# Schematic.net
KiCad netlist of a schematic drawn in Altium Designer
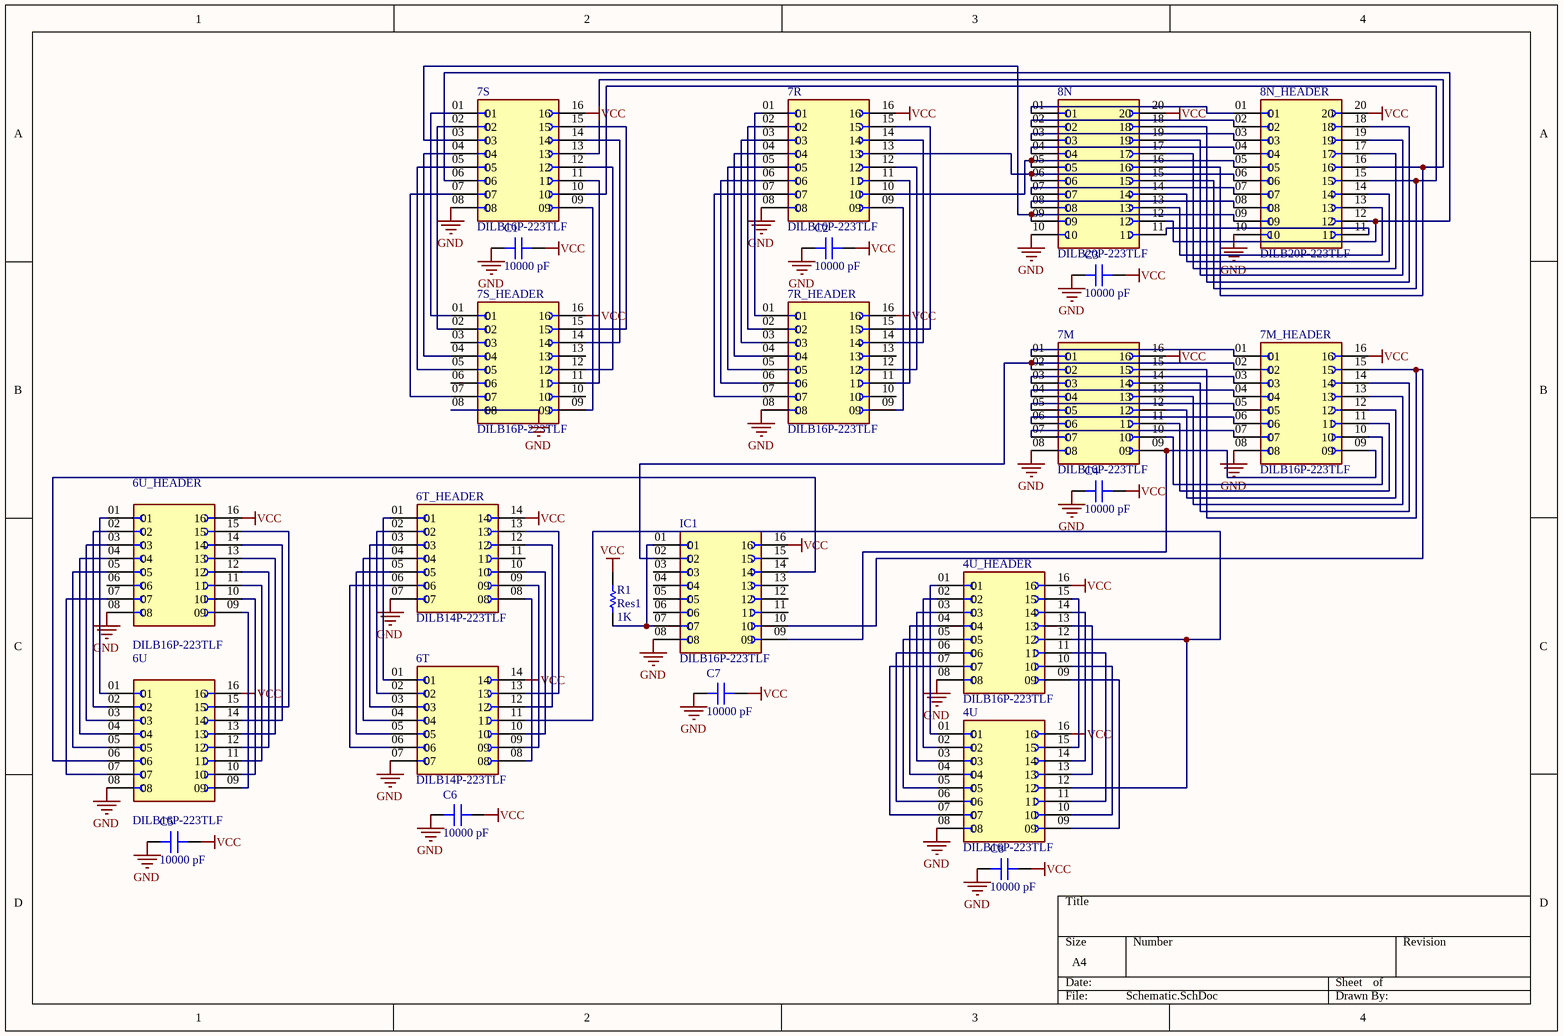
[diagram p0: Schematic.SchDoc]

(export (version "E")
  (design (tool "Eeschema 10.0.6"))
  (components
    (comp (ref "4U")
      (value "DILB16P-223TLF")
      (footprint "AMPHENOL_DILB16P-223TLF")
      (description "DIP Socket, Stamped and Formed")
      (fields (field (name "MF") "Amphenol ICC (FCI)"))
      (libsource (lib "DILB16P-223TLF") (part "DILB16P-223TLF"))
    )
    (comp (ref "4U_HEADER")
      (value "DILB16P-223TLF")
      (footprint "AMPHENOL_DILB16P-223TLF")
      (description "DIP Socket, Stamped and Formed")
      (fields (field (name "MF") "Amphenol ICC (FCI)"))
      (libsource (lib "DILB16P-223TLF") (part "DILB16P-223TLF"))
    )
    (comp (ref "6T")
      (value "DILB14P-223TLF")
      (footprint "AMPHENOL_DILB14P-223TLF")
      (libsource (lib "DILB14P-223TLF") (part "DILB14P-223TLF"))
    )
    (comp (ref "6T_HEADER")
      (value "DILB14P-223TLF")
      (footprint "AMPHENOL_DILB14P-223TLF")
      (libsource (lib "DILB14P-223TLF") (part "DILB14P-223TLF"))
    )
    (comp (ref "6U")
      (value "DILB16P-223TLF")
      (footprint "AMPHENOL_DILB16P-223TLF")
      (description "DIP Socket, Stamped and Formed")
      (fields (field (name "MF") "Amphenol ICC (FCI)"))
      (libsource (lib "DILB16P-223TLF") (part "DILB16P-223TLF"))
    )
    (comp (ref "6U_HEADER")
      (value "DILB16P-223TLF")
      (footprint "AMPHENOL_DILB16P-223TLF")
      (description "DIP Socket, Stamped and Formed")
      (fields (field (name "MF") "Amphenol ICC (FCI)"))
      (libsource (lib "DILB16P-223TLF") (part "DILB16P-223TLF"))
    )
    (comp (ref "7M")
      (value "DILB16P-223TLF")
      (footprint "AMPHENOL_DILB16P-223TLF")
      (description "DIP Socket, Stamped and Formed")
      (fields (field (name "MF") "Amphenol ICC (FCI)"))
      (libsource (lib "DILB16P-223TLF") (part "DILB16P-223TLF"))
    )
    (comp (ref "7M_HEADER")
      (value "DILB16P-223TLF")
      (footprint "AMPHENOL_DILB16P-223TLF")
      (description "DIP Socket, Stamped and Formed")
      (fields (field (name "MF") "Amphenol ICC (FCI)"))
      (libsource (lib "DILB16P-223TLF") (part "DILB16P-223TLF"))
    )
    (comp (ref "7R")
      (value "DILB16P-223TLF")
      (footprint "AMPHENOL_DILB16P-223TLF")
      (description "DIP Socket, Stamped and Formed")
      (fields (field (name "MF") "Amphenol ICC (FCI)"))
      (libsource (lib "DILB16P-223TLF") (part "DILB16P-223TLF"))
    )
    (comp (ref "7R_HEADER")
      (value "DILB16P-223TLF")
      (footprint "AMPHENOL_DILB16P-223TLF")
      (description "DIP Socket, Stamped and Formed")
      (fields (field (name "MF") "Amphenol ICC (FCI)"))
      (libsource (lib "DILB16P-223TLF") (part "DILB16P-223TLF"))
    )
    (comp (ref "7S")
      (value "DILB16P-223TLF")
      (footprint "AMPHENOL_DILB16P-223TLF")
      (description "DIP Socket, Stamped and Formed")
      (fields (field (name "MF") "Amphenol ICC (FCI)"))
      (libsource (lib "DILB16P-223TLF") (part "DILB16P-223TLF"))
    )
    (comp (ref "7S_HEADER")
      (value "DILB16P-223TLF")
      (footprint "AMPHENOL_DILB16P-223TLF")
      (description "DIP Socket, Stamped and Formed")
      (fields (field (name "MF") "Amphenol ICC (FCI)"))
      (libsource (lib "DILB16P-223TLF") (part "DILB16P-223TLF"))
    )
    (comp (ref "8N")
      (value "DILB20P-223TLF")
      (footprint "AMPHENOL_DILB20P-223TLF")
      (description "20 (2 x 10) Pos DIP, 0.3 (7.62mm) Row Spacing Socket Tin Through Hole")
      (fields (field (name "MF") "FCI"))
      (libsource (lib "DILB20P-223TLF") (part "DILB20P-223TLF"))
    )
    (comp (ref "8N_HEADER")
      (value "DILB20P-223TLF")
      (footprint "AMPHENOL_DILB20P-223TLF")
      (description "20 (2 x 10) Pos DIP, 0.3 (7.62mm) Row Spacing Socket Tin Through Hole")
      (fields (field (name "MF") "FCI"))
      (libsource (lib "DILB20P-223TLF") (part "DILB20P-223TLF"))
    )
    (comp (ref "C1")
      (value "10000 pF")
      (footprint "CAP FILM 0805")
      (description "CAP FILM 10000PF 2% 16VDC 0805")
      (fields
        (field (name "PART NUMBER") "ECH-U1C103GX5")
        (field (name "CAPACITANCE") "10000 pF")
        (field (name "MANUFACTURER") "Panasonic Electronic Components")
      )
      (libsource (lib "Celestial Altium Library - altium_library") (part "Capacitor"))
    )
    (comp (ref "C2")
      (value "10000 pF")
      (footprint "CAP FILM 0805")
      (description "CAP FILM 10000PF 2% 16VDC 0805")
      (fields
        (field (name "PART NUMBER") "ECH-U1C103GX5")
        (field (name "CAPACITANCE") "10000 pF")
        (field (name "MANUFACTURER") "Panasonic Electronic Components")
      )
      (libsource (lib "Celestial Altium Library - altium_library") (part "Capacitor"))
    )
    (comp (ref "C3")
      (value "10000 pF")
      (footprint "CAP FILM 0805")
      (description "CAP FILM 10000PF 2% 16VDC 0805")
      (fields
        (field (name "PART NUMBER") "ECH-U1C103GX5")
        (field (name "CAPACITANCE") "10000 pF")
        (field (name "MANUFACTURER") "Panasonic Electronic Components")
      )
      (libsource (lib "Celestial Altium Library - altium_library") (part "Capacitor"))
    )
    (comp (ref "C4")
      (value "10000 pF")
      (footprint "CAP FILM 0805")
      (description "CAP FILM 10000PF 2% 16VDC 0805")
      (fields
        (field (name "PART NUMBER") "ECH-U1C103GX5")
        (field (name "CAPACITANCE") "10000 pF")
        (field (name "MANUFACTURER") "Panasonic Electronic Components")
      )
      (libsource (lib "Celestial Altium Library - altium_library") (part "Capacitor"))
    )
    (comp (ref "C5")
      (value "10000 pF")
      (footprint "CAP FILM 0805")
      (description "CAP FILM 10000PF 2% 16VDC 0805")
      (fields
        (field (name "PART NUMBER") "ECH-U1C103GX5")
        (field (name "CAPACITANCE") "10000 pF")
        (field (name "MANUFACTURER") "Panasonic Electronic Components")
      )
      (libsource (lib "Celestial Altium Library - altium_library") (part "Capacitor"))
    )
    (comp (ref "C6")
      (value "10000 pF")
      (footprint "CAP FILM 0805")
      (description "CAP FILM 10000PF 2% 16VDC 0805")
      (fields
        (field (name "PART NUMBER") "ECH-U1C103GX5")
        (field (name "CAPACITANCE") "10000 pF")
        (field (name "MANUFACTURER") "Panasonic Electronic Components")
      )
      (libsource (lib "Celestial Altium Library - altium_library") (part "Capacitor"))
    )
    (comp (ref "C7")
      (value "10000 pF")
      (footprint "CAP FILM 0805")
      (description "CAP FILM 10000PF 2% 16VDC 0805")
      (fields
        (field (name "PART NUMBER") "ECH-U1C103GX5")
        (field (name "CAPACITANCE") "10000 pF")
        (field (name "MANUFACTURER") "Panasonic Electronic Components")
      )
      (libsource (lib "Celestial Altium Library - altium_library") (part "Capacitor"))
    )
    (comp (ref "C8")
      (value "10000 pF")
      (footprint "CAP FILM 0805")
      (description "CAP FILM 10000PF 2% 16VDC 0805")
      (fields
        (field (name "PART NUMBER") "ECH-U1C103GX5")
        (field (name "CAPACITANCE") "10000 pF")
        (field (name "MANUFACTURER") "Panasonic Electronic Components")
      )
      (libsource (lib "Celestial Altium Library - altium_library") (part "Capacitor"))
    )
    (comp (ref "IC1")
      (value "DILB16P-223TLF")
      (footprint "AMPHENOL_DILB16P-223TLF")
      (description "DIP Socket, Stamped and Formed")
      (fields (field (name "MF") "Amphenol ICC (FCI)"))
      (libsource (lib "DILB16P-223TLF") (part "DILB16P-223TLF"))
    )
    (comp (ref "R1")
      (value "Res1")
      (footprint "AXIAL-0.3")
      (description "Resistor")
      (fields (field (name "ALTIUM_VALUE") "1K") (field (name "PUBLISHER") "Altium Limited"))
      (libsource (lib "Miscellaneous Devices") (part "Res1"))
    )
  )
  (nets
    (net (code "1") (name "GND") (class "Default")
      (node (ref "4U") (pin "08") (pinfunction "08_08") (pintype "passive"))
      (node (ref "4U_HEADER") (pin "08") (pinfunction "08_08") (pintype "passive"))
      (node (ref "6T") (pin "07") (pinfunction "07_07") (pintype "passive"))
      (node (ref "6T_HEADER") (pin "07") (pinfunction "07_07") (pintype "passive"))
      (node (ref "6U") (pin "08") (pinfunction "08_08") (pintype "passive"))
      (node (ref "6U_HEADER") (pin "08") (pinfunction "08_08") (pintype "passive"))
      (node (ref "7M") (pin "08") (pinfunction "08_08") (pintype "passive"))
      (node (ref "7M_HEADER") (pin "08") (pinfunction "08_08") (pintype "passive"))
      (node (ref "7R") (pin "08") (pinfunction "08_08") (pintype "passive"))
      (node (ref "7R_HEADER") (pin "08") (pinfunction "08_08") (pintype "passive"))
      (node (ref "7S") (pin "08") (pinfunction "08_08") (pintype "passive"))
      (node (ref "7S_HEADER") (pin "08") (pinfunction "08_08") (pintype "passive"))
      (node (ref "8N") (pin "10") (pinfunction "10_10") (pintype "passive"))
      (node (ref "8N_HEADER") (pin "10") (pinfunction "10_10") (pintype "passive"))
      (node (ref "C1") (pin "1") (pinfunction "1_1") (pintype "passive"))
      (node (ref "C2") (pin "1") (pinfunction "1_1") (pintype "passive"))
      (node (ref "C3") (pin "1") (pinfunction "1_1") (pintype "passive"))
      (node (ref "C4") (pin "1") (pinfunction "1_1") (pintype "passive"))
      (node (ref "C5") (pin "1") (pinfunction "1_1") (pintype "passive"))
      (node (ref "C6") (pin "1") (pinfunction "1_1") (pintype "passive"))
      (node (ref "C7") (pin "1") (pinfunction "1_1") (pintype "passive"))
      (node (ref "C8") (pin "1") (pinfunction "1_1") (pintype "passive"))
      (node (ref "IC1") (pin "08") (pinfunction "08_08") (pintype "passive"))
    )
    (net (code "2") (name "Net-(4U-Pad01)") (class "Default")
      (node (ref "4U") (pin "01") (pinfunction "01_01") (pintype "passive"))
      (node (ref "4U_HEADER") (pin "01") (pinfunction "01_01") (pintype "passive"))
    )
    (net (code "3") (name "Net-(4U-Pad02)") (class "Default")
      (node (ref "4U") (pin "02") (pinfunction "02_02") (pintype "passive"))
      (node (ref "4U_HEADER") (pin "02") (pinfunction "02_02") (pintype "passive"))
    )
    (net (code "4") (name "Net-(4U-Pad03)") (class "Default")
      (node (ref "4U") (pin "03") (pinfunction "03_03") (pintype "passive"))
      (node (ref "4U_HEADER") (pin "03") (pinfunction "03_03") (pintype "passive"))
    )
    (net (code "5") (name "Net-(4U-Pad04)") (class "Default")
      (node (ref "4U") (pin "04") (pinfunction "04_04") (pintype "passive"))
      (node (ref "4U_HEADER") (pin "04") (pinfunction "04_04") (pintype "passive"))
    )
    (net (code "6") (name "Net-(4U-Pad05)") (class "Default")
      (node (ref "4U") (pin "05") (pinfunction "05_05") (pintype "passive"))
      (node (ref "4U_HEADER") (pin "05") (pinfunction "05_05") (pintype "passive"))
    )
    (net (code "7") (name "Net-(4U-Pad06)") (class "Default")
      (node (ref "4U") (pin "06") (pinfunction "06_06") (pintype "passive"))
      (node (ref "4U_HEADER") (pin "06") (pinfunction "06_06") (pintype "passive"))
    )
    (net (code "8") (name "Net-(4U-Pad07)") (class "Default")
      (node (ref "4U") (pin "07") (pinfunction "07_07") (pintype "passive"))
      (node (ref "4U_HEADER") (pin "07") (pinfunction "07_07") (pintype "passive"))
    )
    (net (code "9") (name "Net-(4U-Pad09)") (class "Default")
      (node (ref "4U") (pin "09") (pinfunction "09_09") (pintype "passive"))
      (node (ref "4U_HEADER") (pin "09") (pinfunction "09_09") (pintype "passive"))
    )
    (net (code "10") (name "Net-(4U-Pad10)") (class "Default")
      (node (ref "4U") (pin "10") (pinfunction "10_10") (pintype "passive"))
      (node (ref "4U_HEADER") (pin "10") (pinfunction "10_10") (pintype "passive"))
    )
    (net (code "11") (name "Net-(4U-Pad11)") (class "Default")
      (node (ref "4U") (pin "11") (pinfunction "11_11") (pintype "passive"))
      (node (ref "4U_HEADER") (pin "11") (pinfunction "11_11") (pintype "passive"))
    )
    (net (code "12") (name "Net-(4U-Pad12)") (class "Default")
      (node (ref "4U") (pin "12") (pinfunction "12_12") (pintype "passive"))
      (node (ref "4U_HEADER") (pin "12") (pinfunction "12_12") (pintype "passive"))
      (node (ref "6T") (pin "11") (pinfunction "11_11") (pintype "passive"))
    )
    (net (code "13") (name "Net-(4U-Pad13)") (class "Default")
      (node (ref "4U") (pin "13") (pinfunction "13_13") (pintype "passive"))
      (node (ref "4U_HEADER") (pin "13") (pinfunction "13_13") (pintype "passive"))
    )
    (net (code "14") (name "Net-(4U-Pad14)") (class "Default")
      (node (ref "4U") (pin "14") (pinfunction "14_14") (pintype "passive"))
      (node (ref "4U_HEADER") (pin "14") (pinfunction "14_14") (pintype "passive"))
    )
    (net (code "15") (name "Net-(4U-Pad15)") (class "Default")
      (node (ref "4U") (pin "15") (pinfunction "15_15") (pintype "passive"))
      (node (ref "4U_HEADER") (pin "15") (pinfunction "15_15") (pintype "passive"))
    )
    (net (code "16") (name "Net-(6T-Pad01)") (class "Default")
      (node (ref "6T") (pin "01") (pinfunction "01_01") (pintype "passive"))
      (node (ref "6T_HEADER") (pin "01") (pinfunction "01_01") (pintype "passive"))
    )
    (net (code "17") (name "Net-(6T-Pad02)") (class "Default")
      (node (ref "6T") (pin "02") (pinfunction "02_02") (pintype "passive"))
      (node (ref "6T_HEADER") (pin "02") (pinfunction "02_02") (pintype "passive"))
    )
    (net (code "18") (name "Net-(6T-Pad03)") (class "Default")
      (node (ref "6T") (pin "03") (pinfunction "03_03") (pintype "passive"))
      (node (ref "6T_HEADER") (pin "03") (pinfunction "03_03") (pintype "passive"))
    )
    (net (code "19") (name "Net-(6T-Pad04)") (class "Default")
      (node (ref "6T") (pin "04") (pinfunction "04_04") (pintype "passive"))
      (node (ref "6T_HEADER") (pin "04") (pinfunction "04_04") (pintype "passive"))
    )
    (net (code "20") (name "Net-(6T-Pad05)") (class "Default")
      (node (ref "6T") (pin "05") (pinfunction "05_05") (pintype "passive"))
      (node (ref "6T_HEADER") (pin "05") (pinfunction "05_05") (pintype "passive"))
    )
    (net (code "21") (name "Net-(6T-Pad06)") (class "Default")
      (node (ref "6T") (pin "06") (pinfunction "06_06") (pintype "passive"))
      (node (ref "6T_HEADER") (pin "06") (pinfunction "06_06") (pintype "passive"))
    )
    (net (code "22") (name "Net-(6T-Pad08)") (class "Default")
      (node (ref "6T") (pin "08") (pinfunction "08_08") (pintype "passive"))
      (node (ref "6T_HEADER") (pin "08") (pinfunction "08_08") (pintype "passive"))
    )
    (net (code "23") (name "Net-(6T-Pad09)") (class "Default")
      (node (ref "6T") (pin "09") (pinfunction "09_09") (pintype "passive"))
      (node (ref "6T_HEADER") (pin "09") (pinfunction "09_09") (pintype "passive"))
    )
    (net (code "24") (name "Net-(6T-Pad10)") (class "Default")
      (node (ref "6T") (pin "10") (pinfunction "10_10") (pintype "passive"))
      (node (ref "6T_HEADER") (pin "10") (pinfunction "10_10") (pintype "passive"))
    )
    (net (code "25") (name "Net-(6T-Pad12)") (class "Default")
      (node (ref "6T") (pin "12") (pinfunction "12_12") (pintype "passive"))
      (node (ref "6T_HEADER") (pin "12") (pinfunction "12_12") (pintype "passive"))
    )
    (net (code "26") (name "Net-(6T-Pad13)") (class "Default")
      (node (ref "6T") (pin "13") (pinfunction "13_13") (pintype "passive"))
      (node (ref "6T_HEADER") (pin "13") (pinfunction "13_13") (pintype "passive"))
    )
    (net (code "27") (name "Net-(6U-Pad01)") (class "Default")
      (node (ref "6U") (pin "01") (pinfunction "01_01") (pintype "passive"))
      (node (ref "6U_HEADER") (pin "01") (pinfunction "01_01") (pintype "passive"))
    )
    (net (code "28") (name "Net-(6U-Pad02)") (class "Default")
      (node (ref "6U") (pin "02") (pinfunction "02_02") (pintype "passive"))
      (node (ref "6U_HEADER") (pin "02") (pinfunction "02_02") (pintype "passive"))
    )
    (net (code "29") (name "Net-(6U-Pad03)") (class "Default")
      (node (ref "6U") (pin "03") (pinfunction "03_03") (pintype "passive"))
      (node (ref "6U_HEADER") (pin "03") (pinfunction "03_03") (pintype "passive"))
    )
    (net (code "30") (name "Net-(6U-Pad04)") (class "Default")
      (node (ref "6U") (pin "04") (pinfunction "04_04") (pintype "passive"))
      (node (ref "6U_HEADER") (pin "04") (pinfunction "04_04") (pintype "passive"))
    )
    (net (code "31") (name "Net-(6U-Pad05)") (class "Default")
      (node (ref "6U") (pin "05") (pinfunction "05_05") (pintype "passive"))
      (node (ref "6U_HEADER") (pin "05") (pinfunction "05_05") (pintype "passive"))
    )
    (net (code "32") (name "Net-(6U-Pad06)") (class "Default")
      (node (ref "6U") (pin "06") (pinfunction "06_06") (pintype "passive"))
      (node (ref "IC1") (pin "14") (pinfunction "14_14") (pintype "passive"))
    )
    (net (code "33") (name "Net-(6U-Pad07)") (class "Default")
      (node (ref "6U") (pin "07") (pinfunction "07_07") (pintype "passive"))
      (node (ref "6U_HEADER") (pin "07") (pinfunction "07_07") (pintype "passive"))
    )
    (net (code "34") (name "Net-(6U-Pad09)") (class "Default")
      (node (ref "6U") (pin "09") (pinfunction "09_09") (pintype "passive"))
      (node (ref "6U_HEADER") (pin "09") (pinfunction "09_09") (pintype "passive"))
    )
    (net (code "35") (name "Net-(6U-Pad10)") (class "Default")
      (node (ref "6U") (pin "10") (pinfunction "10_10") (pintype "passive"))
      (node (ref "6U_HEADER") (pin "10") (pinfunction "10_10") (pintype "passive"))
    )
    (net (code "36") (name "Net-(6U-Pad11)") (class "Default")
      (node (ref "6U") (pin "11") (pinfunction "11_11") (pintype "passive"))
      (node (ref "6U_HEADER") (pin "11") (pinfunction "11_11") (pintype "passive"))
    )
    (net (code "37") (name "Net-(6U-Pad12)") (class "Default")
      (node (ref "6U") (pin "12") (pinfunction "12_12") (pintype "passive"))
      (node (ref "6U_HEADER") (pin "12") (pinfunction "12_12") (pintype "passive"))
    )
    (net (code "38") (name "Net-(6U-Pad13)") (class "Default")
      (node (ref "6U") (pin "13") (pinfunction "13_13") (pintype "passive"))
      (node (ref "6U_HEADER") (pin "13") (pinfunction "13_13") (pintype "passive"))
    )
    (net (code "39") (name "Net-(6U-Pad14)") (class "Default")
      (node (ref "6U") (pin "14") (pinfunction "14_14") (pintype "passive"))
      (node (ref "6U_HEADER") (pin "14") (pinfunction "14_14") (pintype "passive"))
    )
    (net (code "40") (name "Net-(6U-Pad15)") (class "Default")
      (node (ref "6U") (pin "15") (pinfunction "15_15") (pintype "passive"))
      (node (ref "6U_HEADER") (pin "15") (pinfunction "15_15") (pintype "passive"))
    )
    (net (code "41") (name "Net-(7M-Pad01)") (class "Default")
      (node (ref "7M") (pin "01") (pinfunction "01_01") (pintype "passive"))
      (node (ref "7M_HEADER") (pin "01") (pinfunction "01_01") (pintype "passive"))
    )
    (net (code "42") (name "Net-(7M-Pad02)") (class "Default")
      (node (ref "7M") (pin "02") (pinfunction "02_02") (pintype "passive"))
      (node (ref "7M_HEADER") (pin "02") (pinfunction "02_02") (pintype "passive"))
      (node (ref "IC1") (pin "02") (pinfunction "02_02") (pintype "passive"))
    )
    (net (code "43") (name "Net-(7M-Pad03)") (class "Default")
      (node (ref "7M") (pin "03") (pinfunction "03_03") (pintype "passive"))
      (node (ref "7M_HEADER") (pin "03") (pinfunction "03_03") (pintype "passive"))
    )
    (net (code "44") (name "Net-(7M-Pad04)") (class "Default")
      (node (ref "7M") (pin "04") (pinfunction "04_04") (pintype "passive"))
      (node (ref "7M_HEADER") (pin "04") (pinfunction "04_04") (pintype "passive"))
    )
    (net (code "45") (name "Net-(7M-Pad05)") (class "Default")
      (node (ref "7M") (pin "05") (pinfunction "05_05") (pintype "passive"))
      (node (ref "7M_HEADER") (pin "05") (pinfunction "05_05") (pintype "passive"))
    )
    (net (code "46") (name "Net-(7M-Pad06)") (class "Default")
      (node (ref "7M") (pin "06") (pinfunction "06_06") (pintype "passive"))
      (node (ref "7M_HEADER") (pin "06") (pinfunction "06_06") (pintype "passive"))
    )
    (net (code "47") (name "Net-(7M-Pad07)") (class "Default")
      (node (ref "7M") (pin "07") (pinfunction "07_07") (pintype "passive"))
      (node (ref "7M_HEADER") (pin "07") (pinfunction "07_07") (pintype "passive"))
    )
    (net (code "48") (name "Net-(7M-Pad09)") (class "Default")
      (node (ref "7M") (pin "09") (pinfunction "09_09") (pintype "passive"))
      (node (ref "7M_HEADER") (pin "09") (pinfunction "09_09") (pintype "passive"))
      (node (ref "IC1") (pin "09") (pinfunction "09_09") (pintype "passive"))
    )
    (net (code "49") (name "Net-(7M-Pad10)") (class "Default")
      (node (ref "7M") (pin "10") (pinfunction "10_10") (pintype "passive"))
      (node (ref "7M_HEADER") (pin "10") (pinfunction "10_10") (pintype "passive"))
    )
    (net (code "50") (name "Net-(7M-Pad11)") (class "Default")
      (node (ref "7M") (pin "11") (pinfunction "11_11") (pintype "passive"))
      (node (ref "7M_HEADER") (pin "11") (pinfunction "11_11") (pintype "passive"))
    )
    (net (code "51") (name "Net-(7M-Pad12)") (class "Default")
      (node (ref "7M") (pin "12") (pinfunction "12_12") (pintype "passive"))
      (node (ref "7M_HEADER") (pin "12") (pinfunction "12_12") (pintype "passive"))
    )
    (net (code "52") (name "Net-(7M-Pad13)") (class "Default")
      (node (ref "7M") (pin "13") (pinfunction "13_13") (pintype "passive"))
      (node (ref "7M_HEADER") (pin "13") (pinfunction "13_13") (pintype "passive"))
    )
    (net (code "53") (name "Net-(7M-Pad14)") (class "Default")
      (node (ref "7M") (pin "14") (pinfunction "14_14") (pintype "passive"))
      (node (ref "7M_HEADER") (pin "14") (pinfunction "14_14") (pintype "passive"))
    )
    (net (code "54") (name "Net-(7M-Pad15)") (class "Default")
      (node (ref "7M") (pin "15") (pinfunction "15_15") (pintype "passive"))
      (node (ref "7M_HEADER") (pin "15") (pinfunction "15_15") (pintype "passive"))
      (node (ref "IC1") (pin "10") (pinfunction "10_10") (pintype "passive"))
    )
    (net (code "55") (name "Net-(7R-Pad01)") (class "Default")
      (node (ref "7R") (pin "01") (pinfunction "01_01") (pintype "passive"))
      (node (ref "7R_HEADER") (pin "01") (pinfunction "01_01") (pintype "passive"))
    )
    (net (code "56") (name "Net-(7R-Pad02)") (class "Default")
      (node (ref "7R") (pin "02") (pinfunction "02_02") (pintype "passive"))
      (node (ref "7R_HEADER") (pin "02") (pinfunction "02_02") (pintype "passive"))
    )
    (net (code "57") (name "Net-(7R-Pad03)") (class "Default")
      (node (ref "7R") (pin "03") (pinfunction "03_03") (pintype "passive"))
      (node (ref "7R_HEADER") (pin "03") (pinfunction "03_03") (pintype "passive"))
    )
    (net (code "58") (name "Net-(7R-Pad04)") (class "Default")
      (node (ref "7R") (pin "04") (pinfunction "04_04") (pintype "passive"))
      (node (ref "7R_HEADER") (pin "04") (pinfunction "04_04") (pintype "passive"))
    )
    (net (code "59") (name "Net-(7R-Pad05)") (class "Default")
      (node (ref "7R") (pin "05") (pinfunction "05_05") (pintype "passive"))
      (node (ref "7R_HEADER") (pin "05") (pinfunction "05_05") (pintype "passive"))
    )
    (net (code "60") (name "Net-(7R-Pad06)") (class "Default")
      (node (ref "7R") (pin "06") (pinfunction "06_06") (pintype "passive"))
      (node (ref "7R_HEADER") (pin "06") (pinfunction "06_06") (pintype "passive"))
    )
    (net (code "61") (name "Net-(7R-Pad07)") (class "Default")
      (node (ref "7R") (pin "07") (pinfunction "07_07") (pintype "passive"))
      (node (ref "7R_HEADER") (pin "07") (pinfunction "07_07") (pintype "passive"))
    )
    (net (code "62") (name "Net-(7R-Pad09)") (class "Default")
      (node (ref "7R") (pin "09") (pinfunction "09_09") (pintype "passive"))
      (node (ref "7R_HEADER") (pin "09") (pinfunction "09_09") (pintype "passive"))
    )
    (net (code "63") (name "Net-(7R-Pad10)") (class "Default")
      (node (ref "7R") (pin "10") (pinfunction "10_10") (pintype "passive"))
      (node (ref "8N") (pin "05") (pinfunction "05_05") (pintype "passive"))
      (node (ref "8N_HEADER") (pin "05") (pinfunction "05_05") (pintype "passive"))
    )
    (net (code "64") (name "Net-(7R-Pad11)") (class "Default")
      (node (ref "7R") (pin "11") (pinfunction "11_11") (pintype "passive"))
      (node (ref "7R_HEADER") (pin "11") (pinfunction "11_11") (pintype "passive"))
    )
    (net (code "65") (name "Net-(7R-Pad12)") (class "Default")
      (node (ref "7R") (pin "12") (pinfunction "12_12") (pintype "passive"))
      (node (ref "7R_HEADER") (pin "12") (pinfunction "12_12") (pintype "passive"))
    )
    (net (code "66") (name "Net-(7R-Pad13)") (class "Default")
      (node (ref "7R") (pin "13") (pinfunction "13_13") (pintype "passive"))
      (node (ref "8N") (pin "06") (pinfunction "06_06") (pintype "passive"))
      (node (ref "8N_HEADER") (pin "06") (pinfunction "06_06") (pintype "passive"))
    )
    (net (code "67") (name "Net-(7R-Pad14)") (class "Default")
      (node (ref "7R") (pin "14") (pinfunction "14_14") (pintype "passive"))
      (node (ref "7R_HEADER") (pin "14") (pinfunction "14_14") (pintype "passive"))
    )
    (net (code "68") (name "Net-(7R-Pad15)") (class "Default")
      (node (ref "7R") (pin "15") (pinfunction "15_15") (pintype "passive"))
      (node (ref "7R_HEADER") (pin "15") (pinfunction "15_15") (pintype "passive"))
    )
    (net (code "69") (name "Net-(7S-Pad01)") (class "Default")
      (node (ref "7S") (pin "01") (pinfunction "01_01") (pintype "passive"))
      (node (ref "7S_HEADER") (pin "01") (pinfunction "01_01") (pintype "passive"))
    )
    (net (code "70") (name "Net-(7S-Pad02)") (class "Default")
      (node (ref "7S") (pin "02") (pinfunction "02_02") (pintype "passive"))
      (node (ref "7S_HEADER") (pin "02") (pinfunction "02_02") (pintype "passive"))
    )
    (net (code "71") (name "Net-(7S-Pad03)") (class "Default")
      (node (ref "7S") (pin "03") (pinfunction "03_03") (pintype "passive"))
      (node (ref "8N") (pin "09") (pinfunction "09_09") (pintype "passive"))
      (node (ref "8N_HEADER") (pin "09") (pinfunction "09_09") (pintype "passive"))
    )
    (net (code "72") (name "Net-(7S-Pad04)") (class "Default")
      (node (ref "7S") (pin "04") (pinfunction "04_04") (pintype "passive"))
      (node (ref "7S_HEADER") (pin "04") (pinfunction "04_04") (pintype "passive"))
    )
    (net (code "73") (name "Net-(7S-Pad05)") (class "Default")
      (node (ref "7S") (pin "05") (pinfunction "05_05") (pintype "passive"))
      (node (ref "7S_HEADER") (pin "05") (pinfunction "05_05") (pintype "passive"))
    )
    (net (code "74") (name "Net-(7S-Pad06)") (class "Default")
      (node (ref "7S") (pin "06") (pinfunction "06_06") (pintype "passive"))
      (node (ref "8N") (pin "12") (pinfunction "12_12") (pintype "passive"))
      (node (ref "8N_HEADER") (pin "12") (pinfunction "12_12") (pintype "passive"))
    )
    (net (code "75") (name "Net-(7S-Pad07)") (class "Default")
      (node (ref "7S") (pin "07") (pinfunction "07_07") (pintype "passive"))
      (node (ref "7S_HEADER") (pin "07") (pinfunction "07_07") (pintype "passive"))
    )
    (net (code "76") (name "Net-(7S-Pad09)") (class "Default")
      (node (ref "7S") (pin "09") (pinfunction "09_09") (pintype "passive"))
      (node (ref "7S_HEADER") (pin "09") (pinfunction "09_09") (pintype "passive"))
    )
    (net (code "77") (name "Net-(7S-Pad10)") (class "Default")
      (node (ref "7S") (pin "10") (pinfunction "10_10") (pintype "passive"))
      (node (ref "8N") (pin "15") (pinfunction "15_15") (pintype "passive"))
      (node (ref "8N_HEADER") (pin "15") (pinfunction "15_15") (pintype "passive"))
    )
    (net (code "78") (name "Net-(7S-Pad11)") (class "Default")
      (node (ref "7S") (pin "11") (pinfunction "11_11") (pintype "passive"))
      (node (ref "7S_HEADER") (pin "11") (pinfunction "11_11") (pintype "passive"))
    )
    (net (code "79") (name "Net-(7S-Pad12)") (class "Default")
      (node (ref "7S") (pin "12") (pinfunction "12_12") (pintype "passive"))
      (node (ref "7S_HEADER") (pin "12") (pinfunction "12_12") (pintype "passive"))
    )
    (net (code "80") (name "Net-(7S-Pad13)") (class "Default")
      (node (ref "7S") (pin "13") (pinfunction "13_13") (pintype "passive"))
      (node (ref "8N") (pin "16") (pinfunction "16_16") (pintype "passive"))
      (node (ref "8N_HEADER") (pin "16") (pinfunction "16_16") (pintype "passive"))
    )
    (net (code "81") (name "Net-(7S-Pad14)") (class "Default")
      (node (ref "7S") (pin "14") (pinfunction "14_14") (pintype "passive"))
      (node (ref "7S_HEADER") (pin "14") (pinfunction "14_14") (pintype "passive"))
    )
    (net (code "82") (name "Net-(7S-Pad15)") (class "Default")
      (node (ref "7S") (pin "15") (pinfunction "15_15") (pintype "passive"))
      (node (ref "7S_HEADER") (pin "15") (pinfunction "15_15") (pintype "passive"))
    )
    (net (code "83") (name "Net-(8N-Pad01)") (class "Default")
      (node (ref "8N") (pin "01") (pinfunction "01_01") (pintype "passive"))
      (node (ref "8N_HEADER") (pin "01") (pinfunction "01_01") (pintype "passive"))
    )
    (net (code "84") (name "Net-(8N-Pad02)") (class "Default")
      (node (ref "8N") (pin "02") (pinfunction "02_02") (pintype "passive"))
      (node (ref "8N_HEADER") (pin "02") (pinfunction "02_02") (pintype "passive"))
    )
    (net (code "85") (name "Net-(8N-Pad03)") (class "Default")
      (node (ref "8N") (pin "03") (pinfunction "03_03") (pintype "passive"))
      (node (ref "8N_HEADER") (pin "03") (pinfunction "03_03") (pintype "passive"))
    )
    (net (code "86") (name "Net-(8N-Pad04)") (class "Default")
      (node (ref "8N") (pin "04") (pinfunction "04_04") (pintype "passive"))
      (node (ref "8N_HEADER") (pin "04") (pinfunction "04_04") (pintype "passive"))
    )
    (net (code "87") (name "Net-(8N-Pad07)") (class "Default")
      (node (ref "8N") (pin "07") (pinfunction "07_07") (pintype "passive"))
      (node (ref "8N_HEADER") (pin "07") (pinfunction "07_07") (pintype "passive"))
    )
    (net (code "88") (name "Net-(8N-Pad08)") (class "Default")
      (node (ref "8N") (pin "08") (pinfunction "08_08") (pintype "passive"))
      (node (ref "8N_HEADER") (pin "08") (pinfunction "08_08") (pintype "passive"))
    )
    (net (code "89") (name "Net-(8N-Pad11)") (class "Default")
      (node (ref "8N") (pin "11") (pinfunction "11_11") (pintype "passive"))
      (node (ref "8N_HEADER") (pin "11") (pinfunction "11_11") (pintype "passive"))
    )
    (net (code "90") (name "Net-(8N-Pad13)") (class "Default")
      (node (ref "8N") (pin "13") (pinfunction "13_13") (pintype "passive"))
      (node (ref "8N_HEADER") (pin "13") (pinfunction "13_13") (pintype "passive"))
    )
    (net (code "91") (name "Net-(8N-Pad14)") (class "Default")
      (node (ref "8N") (pin "14") (pinfunction "14_14") (pintype "passive"))
      (node (ref "8N_HEADER") (pin "14") (pinfunction "14_14") (pintype "passive"))
    )
    (net (code "92") (name "Net-(8N-Pad17)") (class "Default")
      (node (ref "8N") (pin "17") (pinfunction "17_17") (pintype "passive"))
      (node (ref "8N_HEADER") (pin "17") (pinfunction "17_17") (pintype "passive"))
    )
    (net (code "93") (name "Net-(8N-Pad18)") (class "Default")
      (node (ref "8N") (pin "18") (pinfunction "18_18") (pintype "passive"))
      (node (ref "8N_HEADER") (pin "18") (pinfunction "18_18") (pintype "passive"))
    )
    (net (code "94") (name "Net-(8N-Pad19)") (class "Default")
      (node (ref "8N") (pin "19") (pinfunction "19_19") (pintype "passive"))
      (node (ref "8N_HEADER") (pin "19") (pinfunction "19_19") (pintype "passive"))
    )
    (net (code "95") (name "Net-(IC1-Pad01)") (class "Default")
      (node (ref "IC1") (pin "01") (pinfunction "01_01") (pintype "passive"))
      (node (ref "IC1") (pin "07") (pinfunction "07_07") (pintype "passive"))
      (node (ref "R1") (pin "2") (pinfunction "2_2") (pintype "passive"))
    )
    (net (code "96") (name "VCC") (class "Default")
      (node (ref "4U") (pin "16") (pinfunction "16_16") (pintype "passive"))
      (node (ref "4U_HEADER") (pin "16") (pinfunction "16_16") (pintype "passive"))
      (node (ref "6T") (pin "14") (pinfunction "14_14") (pintype "passive"))
      (node (ref "6T_HEADER") (pin "14") (pinfunction "14_14") (pintype "passive"))
      (node (ref "6U") (pin "16") (pinfunction "16_16") (pintype "passive"))
      (node (ref "6U_HEADER") (pin "16") (pinfunction "16_16") (pintype "passive"))
      (node (ref "7M") (pin "16") (pinfunction "16_16") (pintype "passive"))
      (node (ref "7M_HEADER") (pin "16") (pinfunction "16_16") (pintype "passive"))
      (node (ref "7R") (pin "16") (pinfunction "16_16") (pintype "passive"))
      (node (ref "7R_HEADER") (pin "16") (pinfunction "16_16") (pintype "passive"))
      (node (ref "7S") (pin "16") (pinfunction "16_16") (pintype "passive"))
      (node (ref "7S_HEADER") (pin "16") (pinfunction "16_16") (pintype "passive"))
      (node (ref "8N") (pin "20") (pinfunction "20_20") (pintype "passive"))
      (node (ref "8N_HEADER") (pin "20") (pinfunction "20_20") (pintype "passive"))
      (node (ref "C1") (pin "2") (pinfunction "2_2") (pintype "passive"))
      (node (ref "C2") (pin "2") (pinfunction "2_2") (pintype "passive"))
      (node (ref "C3") (pin "2") (pinfunction "2_2") (pintype "passive"))
      (node (ref "C4") (pin "2") (pinfunction "2_2") (pintype "passive"))
      (node (ref "C5") (pin "2") (pinfunction "2_2") (pintype "passive"))
      (node (ref "C6") (pin "2") (pinfunction "2_2") (pintype "passive"))
      (node (ref "C7") (pin "2") (pinfunction "2_2") (pintype "passive"))
      (node (ref "C8") (pin "2") (pinfunction "2_2") (pintype "passive"))
      (node (ref "IC1") (pin "16") (pinfunction "16_16") (pintype "passive"))
      (node (ref "R1") (pin "1") (pinfunction "1_1") (pintype "passive"))
    )
    (net (code "97") (name "unconnected-(6T_HEADER-Pad11)") (class "Default")
      (node (ref "6T_HEADER") (pin "11") (pinfunction "11_11") (pintype "passive"))
    )
    (net (code "98") (name "unconnected-(6U_HEADER-Pad06)") (class "Default")
      (node (ref "6U_HEADER") (pin "06") (pinfunction "06_06") (pintype "passive"))
    )
    (net (code "99") (name "unconnected-(7R_HEADER-Pad10)") (class "Default")
      (node (ref "7R_HEADER") (pin "10") (pinfunction "10_10") (pintype "passive"))
    )
    (net (code "100") (name "unconnected-(7R_HEADER-Pad13)") (class "Default")
      (node (ref "7R_HEADER") (pin "13") (pinfunction "13_13") (pintype "passive"))
    )
    (net (code "101") (name "unconnected-(7S_HEADER-Pad03)") (class "Default")
      (node (ref "7S_HEADER") (pin "03") (pinfunction "03_03") (pintype "passive"))
    )
    (net (code "102") (name "unconnected-(7S_HEADER-Pad06)") (class "Default")
      (node (ref "7S_HEADER") (pin "06") (pinfunction "06_06") (pintype "passive"))
    )
    (net (code "103") (name "unconnected-(7S_HEADER-Pad10)") (class "Default")
      (node (ref "7S_HEADER") (pin "10") (pinfunction "10_10") (pintype "passive"))
    )
    (net (code "104") (name "unconnected-(7S_HEADER-Pad13)") (class "Default")
      (node (ref "7S_HEADER") (pin "13") (pinfunction "13_13") (pintype "passive"))
    )
    (net (code "105") (name "unconnected-(IC1-Pad03)") (class "Default")
      (node (ref "IC1") (pin "03") (pinfunction "03_03") (pintype "passive"))
    )
    (net (code "106") (name "unconnected-(IC1-Pad04)") (class "Default")
      (node (ref "IC1") (pin "04") (pinfunction "04_04") (pintype "passive"))
    )
    (net (code "107") (name "unconnected-(IC1-Pad05)") (class "Default")
      (node (ref "IC1") (pin "05") (pinfunction "05_05") (pintype "passive"))
    )
    (net (code "108") (name "unconnected-(IC1-Pad06)") (class "Default")
      (node (ref "IC1") (pin "06") (pinfunction "06_06") (pintype "passive"))
    )
    (net (code "109") (name "unconnected-(IC1-Pad11)") (class "Default")
      (node (ref "IC1") (pin "11") (pinfunction "11_11") (pintype "passive"))
    )
    (net (code "110") (name "unconnected-(IC1-Pad12)") (class "Default")
      (node (ref "IC1") (pin "12") (pinfunction "12_12") (pintype "passive"))
    )
    (net (code "111") (name "unconnected-(IC1-Pad13)") (class "Default")
      (node (ref "IC1") (pin "13") (pinfunction "13_13") (pintype "passive"))
    )
    (net (code "112") (name "unconnected-(IC1-Pad15)") (class "Default")
      (node (ref "IC1") (pin "15") (pinfunction "15_15") (pintype "passive"))
    )
  )
)
